# ExtendBoardSheet.net
KiCad netlist of a schematic drawn in Altium Designer
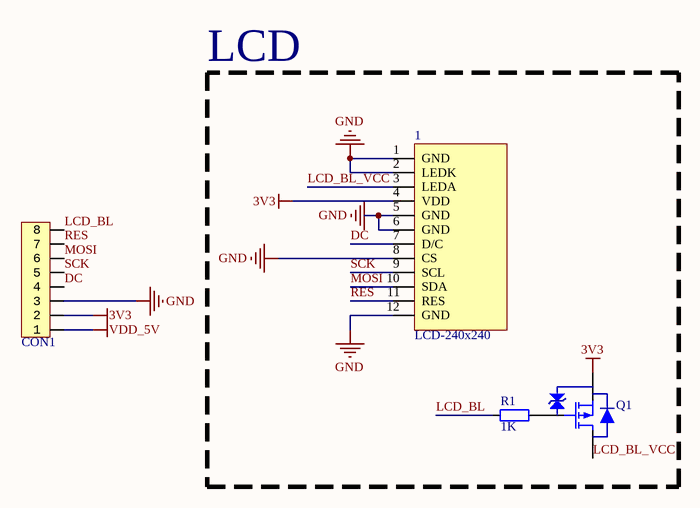
[diagram p0: ExtendBoardSheet.SchDoc]

(export (version "E")
  (design (tool "Eeschema 10.0.6"))
  (components
    (comp (ref "1")
      (value "LCD-240x240")
      (footprint "LCD-240x240-NoHole")
      (description "显示屏")
      (libsource (lib "ExtendBoard") (part "LCD-240x240"))
    )
    (comp (ref "CON1")
      (value "FFC_0.5_8")
      (footprint "FFC_0.5_8")
      (description "FFC")
      (libsource (lib "ExtendBoard") (part "FFC_0.5_8"))
    )
    (comp (ref "Q1")
      (value "AO3415A")
      (footprint "SOT23-3")
      (description "MOSFET")
      (fields (field (name "PUBLISHER") "Altium Limited"))
      (libsource (lib "ExtendBoard") (part "AO3415A"))
    )
    (comp (ref "R1")
      (value "1K")
      (footprint "RES_0402")
      (description "Resistor")
      (libsource (lib "ExtendBoard") (part "电阻-0402"))
    )
  )
  (nets
    (net (code "1") (name "/DC") (class "Default")
      (node (ref "1") (pin "7") (pinfunction "D/C_7") (pintype "passive"))
      (node (ref "CON1") (pin "4") (pinfunction "4_4") (pintype "passive"))
    )
    (net (code "2") (name "/LCD_BL") (class "Default")
      (node (ref "CON1") (pin "8") (pinfunction "8_8") (pintype "passive"))
      (node (ref "R1") (pin "1") (pinfunction "1_1") (pintype "passive"))
    )
    (net (code "3") (name "/LCD_BL_VCC") (class "Default")
      (node (ref "1") (pin "3") (pinfunction "LEDA_3") (pintype "passive"))
      (node (ref "Q1") (pin "3") (pinfunction "D_3") (pintype "passive"))
    )
    (net (code "4") (name "/MOSI") (class "Default")
      (node (ref "1") (pin "10") (pinfunction "SDA_10") (pintype "passive"))
      (node (ref "CON1") (pin "6") (pinfunction "6_6") (pintype "passive"))
    )
    (net (code "5") (name "/RES") (class "Default")
      (node (ref "1") (pin "11") (pinfunction "RES_11") (pintype "passive"))
      (node (ref "CON1") (pin "7") (pinfunction "7_7") (pintype "passive"))
    )
    (net (code "6") (name "/SCK") (class "Default")
      (node (ref "1") (pin "9") (pinfunction "SCL_9") (pintype "passive"))
      (node (ref "CON1") (pin "5") (pinfunction "5_5") (pintype "passive"))
    )
    (net (code "7") (name "3V3") (class "Default")
      (node (ref "1") (pin "4") (pinfunction "VDD_4") (pintype "passive"))
      (node (ref "CON1") (pin "2") (pinfunction "2_2") (pintype "passive"))
      (node (ref "Q1") (pin "2") (pinfunction "S_2") (pintype "passive"))
    )
    (net (code "8") (name "GND") (class "Default")
      (node (ref "1") (pin "1") (pinfunction "GND_1") (pintype "passive"))
      (node (ref "1") (pin "12") (pinfunction "GND_12") (pintype "passive"))
      (node (ref "1") (pin "2") (pinfunction "LEDK_2") (pintype "passive"))
      (node (ref "1") (pin "5") (pinfunction "GND_5") (pintype "passive"))
      (node (ref "1") (pin "6") (pinfunction "GND_6") (pintype "passive"))
      (node (ref "1") (pin "8") (pinfunction "CS_8") (pintype "passive"))
      (node (ref "CON1") (pin "3") (pinfunction "3_3") (pintype "passive"))
    )
    (net (code "9") (name "Net-(Q1-G)") (class "Default")
      (node (ref "Q1") (pin "1") (pinfunction "G_1") (pintype "passive"))
      (node (ref "R1") (pin "2") (pinfunction "2_2") (pintype "passive"))
    )
    (net (code "10") (name "VDD_5V") (class "Default")
      (node (ref "CON1") (pin "1") (pinfunction "1_1") (pintype "passive"))
    )
  )
)
